# STM32.net
KiCad netlist of a schematic drawn in EAGLE
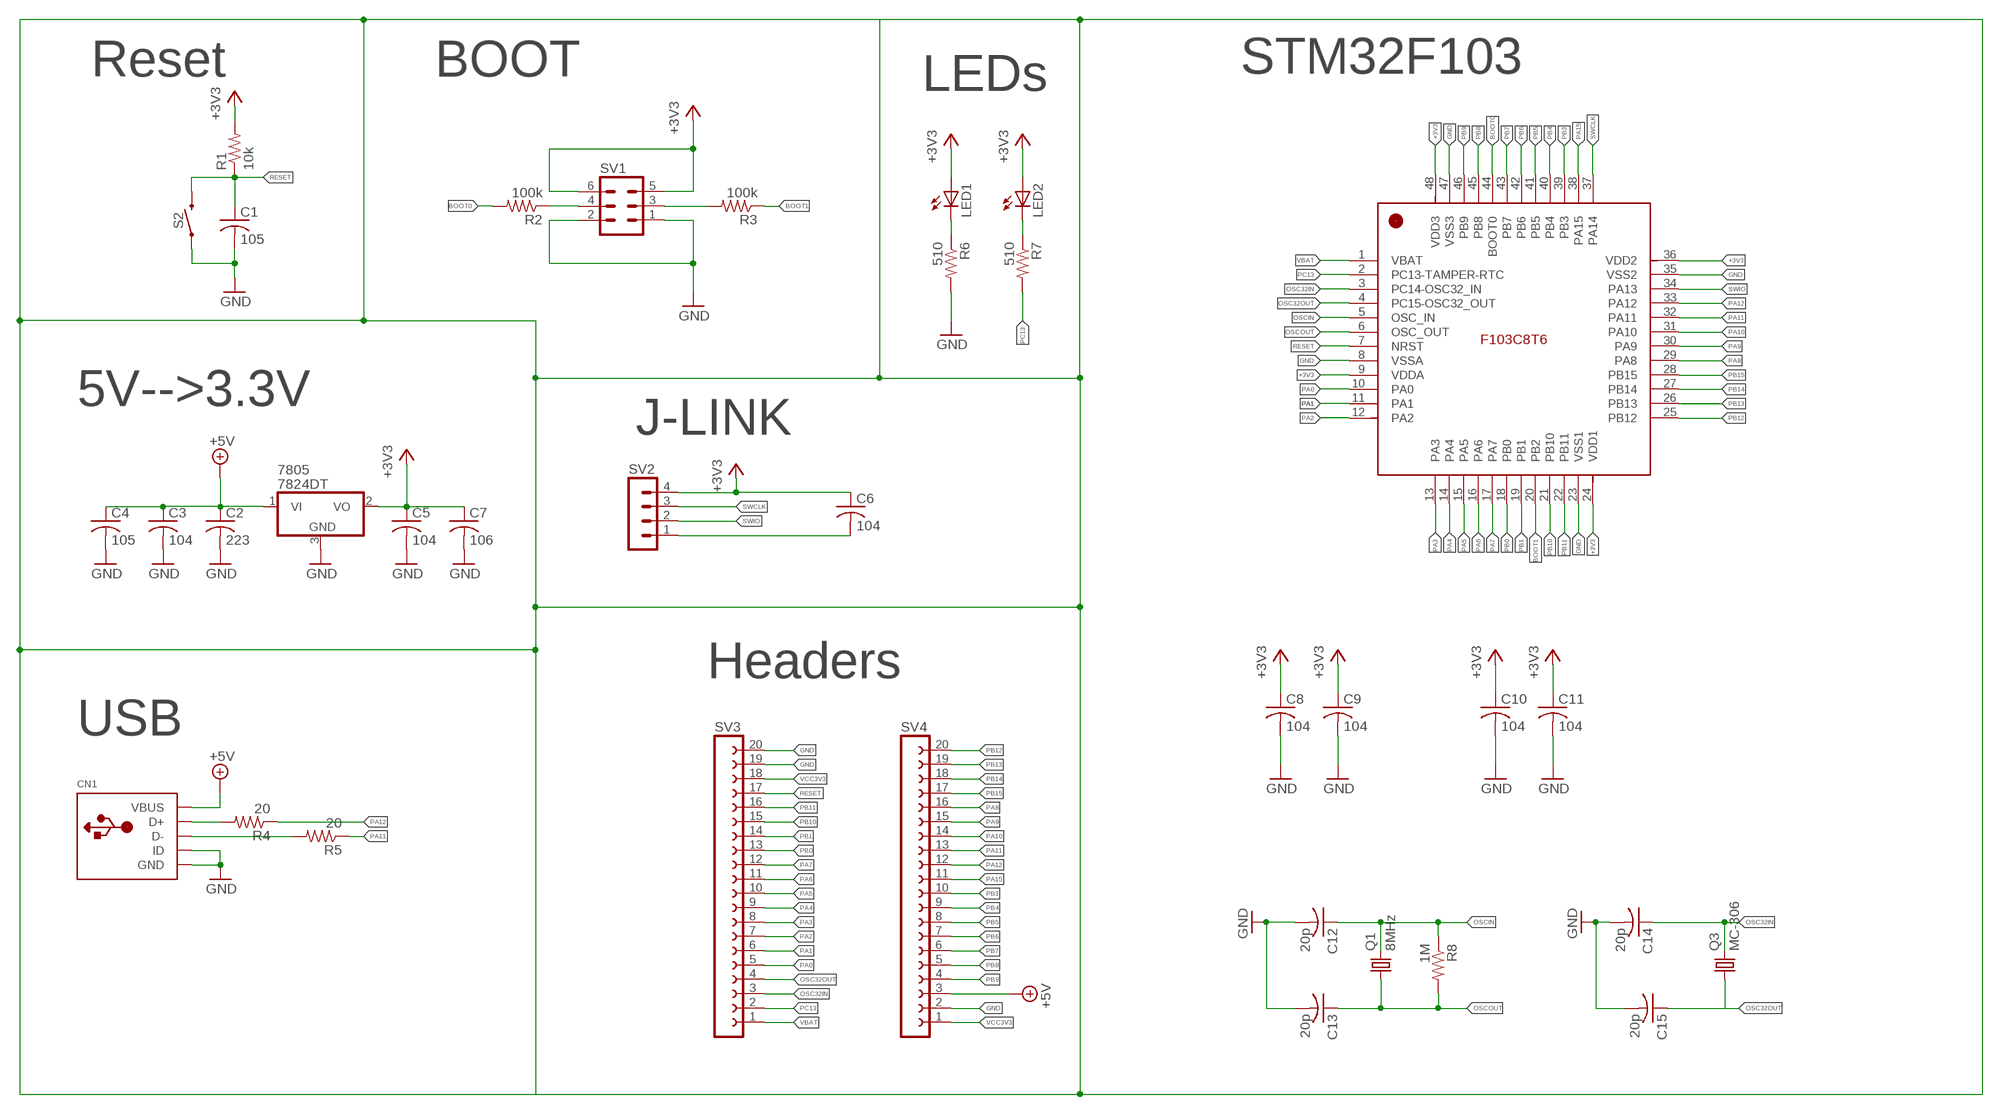
[diagram p0: schematic, sheet 1]

(export (version "E")
  (design (tool "Eeschema 10.0.6"))
  (components
    (comp (ref "7805")
      (value "7824DT")
      (footprint "eagle-import:TO252")
      (libsource (lib "eagle-import") (part "78DT24"))
    )
    (comp (ref "C1")
      (value "105")
      (footprint "eagle-import:C0603")
      (libsource (lib "eagle-import") (part "C-USC0603"))
    )
    (comp (ref "C2")
      (value "223")
      (footprint "eagle-import:C0603")
      (libsource (lib "eagle-import") (part "C-USC0603"))
    )
    (comp (ref "C3")
      (value "104")
      (footprint "eagle-import:C0603")
      (libsource (lib "eagle-import") (part "C-USC0603"))
    )
    (comp (ref "C4")
      (value "105")
      (footprint "eagle-import:C0805")
      (libsource (lib "eagle-import") (part "C-USC0805"))
    )
    (comp (ref "C5")
      (value "104")
      (footprint "eagle-import:C0603")
      (libsource (lib "eagle-import") (part "C-USC0603"))
    )
    (comp (ref "C6")
      (value "104")
      (footprint "eagle-import:C0603")
      (libsource (lib "eagle-import") (part "C-USC0603"))
    )
    (comp (ref "C7")
      (value "106")
      (footprint "eagle-import:C0805")
      (libsource (lib "eagle-import") (part "C-USC0805"))
    )
    (comp (ref "C8")
      (value "104")
      (footprint "eagle-import:C0603")
      (libsource (lib "eagle-import") (part "C-USC0603"))
    )
    (comp (ref "C9")
      (value "104")
      (footprint "eagle-import:C0603")
      (libsource (lib "eagle-import") (part "C-USC0603"))
    )
    (comp (ref "C10")
      (value "104")
      (footprint "eagle-import:C0603")
      (libsource (lib "eagle-import") (part "C-USC0603"))
    )
    (comp (ref "C11")
      (value "104")
      (footprint "eagle-import:C0603")
      (libsource (lib "eagle-import") (part "C-USC0603"))
    )
    (comp (ref "C12")
      (value "20p")
      (footprint "eagle-import:C0603")
      (libsource (lib "eagle-import") (part "C-USC0603"))
    )
    (comp (ref "C13")
      (value "20p")
      (footprint "eagle-import:C0603")
      (libsource (lib "eagle-import") (part "C-USC0603"))
    )
    (comp (ref "C14")
      (value "20p")
      (footprint "eagle-import:C0603")
      (libsource (lib "eagle-import") (part "C-USC0603"))
    )
    (comp (ref "C15")
      (value "20p")
      (footprint "eagle-import:C0603")
      (libsource (lib "eagle-import") (part "C-USC0603"))
    )
    (comp (ref "CN1")
      (value "USBMINIB")
      (footprint "eagle-import:USB-MINIB")
      (libsource (lib "eagle-import") (part "USBMINIB"))
    )
    (comp (ref "LED1")
      (value "LEDCHIPLED_0805")
      (footprint "eagle-import:CHIPLED_0805")
      (libsource (lib "eagle-import") (part "LEDCHIPLED_0805"))
    )
    (comp (ref "LED2")
      (value "LEDCHIPLED_0805")
      (footprint "eagle-import:CHIPLED_0805")
      (libsource (lib "eagle-import") (part "LEDCHIPLED_0805"))
    )
    (comp (ref "Q1")
      (value "8MHz")
      (footprint "eagle-import:HC49U70")
      (libsource (lib "eagle-import") (part "CRYTALHC49U70"))
    )
    (comp (ref "Q3")
      (value "MC-306")
      (footprint "eagle-import:MC-306")
      (fields (field (name "MPN") "MC-306 60.0KHZ  100PPM ,12.5PF"))
      (libsource (lib "eagle-import") (part "MC-306"))
    )
    (comp (ref "R1")
      (value "10k")
      (footprint "eagle-import:R0603")
      (libsource (lib "eagle-import") (part "R-US_R0603"))
    )
    (comp (ref "R2")
      (value "100k")
      (footprint "eagle-import:R0603")
      (libsource (lib "eagle-import") (part "R-US_R0603"))
    )
    (comp (ref "R3")
      (value "100k")
      (footprint "eagle-import:R0603")
      (libsource (lib "eagle-import") (part "R-US_R0603"))
    )
    (comp (ref "R4")
      (value "20")
      (footprint "eagle-import:R0603")
      (libsource (lib "eagle-import") (part "R-US_R0603"))
    )
    (comp (ref "R5")
      (value "20")
      (footprint "eagle-import:R0603")
      (libsource (lib "eagle-import") (part "R-US_R0603"))
    )
    (comp (ref "R6")
      (value "510")
      (footprint "eagle-import:R0603")
      (libsource (lib "eagle-import") (part "R-US_R0603"))
    )
    (comp (ref "R7")
      (value "510")
      (footprint "eagle-import:R0603")
      (libsource (lib "eagle-import") (part "R-US_R0603"))
    )
    (comp (ref "R8")
      (value "1M")
      (footprint "eagle-import:R0603")
      (libsource (lib "eagle-import") (part "R-US_R0603"))
    )
    (comp (ref "S2")
      (value "MOMENTARY-SWITCH-SPST-SMD-5.2-REDUNDANT")
      (footprint "eagle-import:TACTILE_SWITCH_SMD_5.2MM")
      (libsource (lib "eagle-import") (part "MOMENTARY-SWITCH-SPST-SMD-5.2-REDUNDANT"))
    )
    (comp (ref "SV1")
      (value "MA03-2")
      (footprint "eagle-import:MA03-2")
      (libsource (lib "eagle-import") (part "MA03-2"))
    )
    (comp (ref "SV2")
      (value "MA04-1")
      (footprint "eagle-import:MA04-1")
      (libsource (lib "eagle-import") (part "MA04-1"))
    )
    (comp (ref "SV3")
      (value "FE20-1")
      (footprint "eagle-import:FE20")
      (libsource (lib "eagle-import") (part "FE20-1"))
    )
    (comp (ref "SV4")
      (value "FE20-1")
      (footprint "eagle-import:FE20")
      (libsource (lib "eagle-import") (part "FE20-1"))
    )
    (comp (ref "U$1")
      (value "STM32F103C8T6")
      (footprint "eagle-import:LQFP48_7X7MM_0.5MMPP")
      (fields (field (name "MF") "STMicroelectronics"))
      (libsource (lib "eagle-import") (part "STM32F103C8T6"))
    )
  )
  (nets
    (net (code "1") (name "+3V3") (class "Default")
      (node (ref "7805") (pin "2") (pinfunction "VO_2") (pintype "passive"))
      (node (ref "C10") (pin "1") (pinfunction "1_1") (pintype "passive"))
      (node (ref "C11") (pin "1") (pinfunction "1_1") (pintype "passive"))
      (node (ref "C5") (pin "1") (pinfunction "1_1") (pintype "passive"))
      (node (ref "C6") (pin "1") (pinfunction "1_1") (pintype "passive"))
      (node (ref "C7") (pin "1") (pinfunction "1_1") (pintype "passive"))
      (node (ref "C8") (pin "1") (pinfunction "1_1") (pintype "passive"))
      (node (ref "C9") (pin "1") (pinfunction "1_1") (pintype "passive"))
      (node (ref "LED1") (pin "A") (pinfunction "A_A") (pintype "passive"))
      (node (ref "LED2") (pin "A") (pinfunction "A_A") (pintype "passive"))
      (node (ref "R1") (pin "2") (pinfunction "2_2") (pintype "passive"))
      (node (ref "SV1") (pin "5") (pinfunction "5_5") (pintype "passive"))
      (node (ref "SV1") (pin "6") (pinfunction "6_6") (pintype "passive"))
      (node (ref "SV2") (pin "4") (pinfunction "4_4") (pintype "passive"))
      (node (ref "U$1") (pin "24") (pinfunction "VDD1_24") (pintype "bidirectional"))
      (node (ref "U$1") (pin "36") (pinfunction "VDD2_36") (pintype "bidirectional"))
      (node (ref "U$1") (pin "48") (pinfunction "VDD3_48") (pintype "bidirectional"))
      (node (ref "U$1") (pin "9") (pinfunction "VDDA_9") (pintype "bidirectional"))
    )
    (net (code "2") (name "+5V") (class "Default")
      (node (ref "7805") (pin "1") (pinfunction "VI_1") (pintype "input"))
      (node (ref "C2") (pin "1") (pinfunction "1_1") (pintype "passive"))
      (node (ref "C3") (pin "1") (pinfunction "1_1") (pintype "passive"))
      (node (ref "C4") (pin "1") (pinfunction "1_1") (pintype "passive"))
      (node (ref "CN1") (pin "VBUS") (pinfunction "VBUS_VBUS") (pintype "power_in"))
      (node (ref "SV4") (pin "3") (pinfunction "3_3") (pintype "passive"))
    )
    (net (code "3") (name "BOOT0") (class "Default")
      (node (ref "R2") (pin "2") (pinfunction "2_2") (pintype "passive"))
      (node (ref "U$1") (pin "44") (pinfunction "BOOT0_44") (pintype "bidirectional"))
    )
    (net (code "4") (name "BOOT1") (class "Default")
      (node (ref "R3") (pin "1") (pinfunction "1_1") (pintype "passive"))
      (node (ref "U$1") (pin "20") (pinfunction "PB2_20") (pintype "bidirectional"))
    )
    (net (code "5") (name "GND") (class "Default")
      (node (ref "7805") (pin "3") (pinfunction "GND_3") (pintype "passive"))
      (node (ref "C1") (pin "2") (pinfunction "2_2") (pintype "passive"))
      (node (ref "C10") (pin "2") (pinfunction "2_2") (pintype "passive"))
      (node (ref "C11") (pin "2") (pinfunction "2_2") (pintype "passive"))
      (node (ref "C12") (pin "2") (pinfunction "2_2") (pintype "passive"))
      (node (ref "C13") (pin "2") (pinfunction "2_2") (pintype "passive"))
      (node (ref "C14") (pin "2") (pinfunction "2_2") (pintype "passive"))
      (node (ref "C15") (pin "2") (pinfunction "2_2") (pintype "passive"))
      (node (ref "C2") (pin "2") (pinfunction "2_2") (pintype "passive"))
      (node (ref "C3") (pin "2") (pinfunction "2_2") (pintype "passive"))
      (node (ref "C4") (pin "2") (pinfunction "2_2") (pintype "passive"))
      (node (ref "C5") (pin "2") (pinfunction "2_2") (pintype "passive"))
      (node (ref "C7") (pin "2") (pinfunction "2_2") (pintype "passive"))
      (node (ref "C8") (pin "2") (pinfunction "2_2") (pintype "passive"))
      (node (ref "C9") (pin "2") (pinfunction "2_2") (pintype "passive"))
      (node (ref "CN1") (pin "GND") (pinfunction "GND_GND") (pintype "power_in"))
      (node (ref "CN1") (pin "ID") (pinfunction "ID_ID") (pintype "bidirectional"))
      (node (ref "R6") (pin "2") (pinfunction "2_2") (pintype "passive"))
      (node (ref "S2") (pin "1") (pinfunction "1_1") (pintype "passive"))
      (node (ref "S2") (pin "2") (pinfunction "1_2") (pintype "passive"))
      (node (ref "SV1") (pin "1") (pinfunction "1_1") (pintype "passive"))
      (node (ref "SV1") (pin "2") (pinfunction "2_2") (pintype "passive"))
      (node (ref "SV3") (pin "19") (pinfunction "19_19") (pintype "passive"))
      (node (ref "SV3") (pin "20") (pinfunction "20_20") (pintype "passive"))
      (node (ref "SV4") (pin "2") (pinfunction "2_2") (pintype "passive"))
      (node (ref "U$1") (pin "23") (pinfunction "VSS1_23") (pintype "bidirectional"))
      (node (ref "U$1") (pin "35") (pinfunction "VSS2_35") (pintype "bidirectional"))
      (node (ref "U$1") (pin "47") (pinfunction "VSS3_47") (pintype "bidirectional"))
      (node (ref "U$1") (pin "8") (pinfunction "VSSA_8") (pintype "bidirectional"))
    )
    (net (code "6") (name "Net-(C6-Pad2)") (class "Default")
      (node (ref "C6") (pin "2") (pinfunction "2_2") (pintype "passive"))
      (node (ref "SV2") (pin "1") (pinfunction "1_1") (pintype "passive"))
    )
    (net (code "7") (name "Net-(CN1-PadD+)") (class "Default")
      (node (ref "CN1") (pin "D+") (pinfunction "D+_D+") (pintype "bidirectional"))
      (node (ref "R4") (pin "2") (pinfunction "2_2") (pintype "passive"))
    )
    (net (code "8") (name "Net-(CN1-PadD-)") (class "Default")
      (node (ref "CN1") (pin "D-") (pinfunction "D-_D-") (pintype "bidirectional"))
      (node (ref "R5") (pin "2") (pinfunction "2_2") (pintype "passive"))
    )
    (net (code "9") (name "Net-(LED1-PadC)") (class "Default")
      (node (ref "LED1") (pin "C") (pinfunction "C_C") (pintype "passive"))
      (node (ref "R6") (pin "1") (pinfunction "1_1") (pintype "passive"))
    )
    (net (code "10") (name "Net-(LED2-PadC)") (class "Default")
      (node (ref "LED2") (pin "C") (pinfunction "C_C") (pintype "passive"))
      (node (ref "R7") (pin "1") (pinfunction "1_1") (pintype "passive"))
    )
    (net (code "11") (name "Net-(R2-Pad1)") (class "Default")
      (node (ref "R2") (pin "1") (pinfunction "1_1") (pintype "passive"))
      (node (ref "SV1") (pin "4") (pinfunction "4_4") (pintype "passive"))
    )
    (net (code "12") (name "Net-(R3-Pad2)") (class "Default")
      (node (ref "R3") (pin "2") (pinfunction "2_2") (pintype "passive"))
      (node (ref "SV1") (pin "3") (pinfunction "3_3") (pintype "passive"))
    )
    (net (code "13") (name "OSC32IN") (class "Default")
      (node (ref "C14") (pin "1") (pinfunction "1_1") (pintype "passive"))
      (node (ref "Q3") (pin "4") (pinfunction "2_4") (pintype "passive"))
      (node (ref "SV3") (pin "3") (pinfunction "3_3") (pintype "passive"))
      (node (ref "U$1") (pin "3") (pinfunction "PC14-OSC32_IN_3") (pintype "bidirectional"))
    )
    (net (code "14") (name "OSC32OUT") (class "Default")
      (node (ref "C15") (pin "1") (pinfunction "1_1") (pintype "passive"))
      (node (ref "Q3") (pin "1") (pinfunction "1_1") (pintype "passive"))
      (node (ref "SV3") (pin "4") (pinfunction "4_4") (pintype "passive"))
      (node (ref "U$1") (pin "4") (pinfunction "PC15-OSC32_OUT_4") (pintype "bidirectional"))
    )
    (net (code "15") (name "OSCIN") (class "Default")
      (node (ref "C12") (pin "1") (pinfunction "1_1") (pintype "passive"))
      (node (ref "Q1") (pin "2") (pinfunction "2_2") (pintype "passive"))
      (node (ref "R8") (pin "1") (pinfunction "1_1") (pintype "passive"))
      (node (ref "U$1") (pin "5") (pinfunction "OSC_IN_5") (pintype "bidirectional"))
    )
    (net (code "16") (name "OSCOUT") (class "Default")
      (node (ref "C13") (pin "1") (pinfunction "1_1") (pintype "passive"))
      (node (ref "Q1") (pin "1") (pinfunction "1_1") (pintype "passive"))
      (node (ref "R8") (pin "2") (pinfunction "2_2") (pintype "passive"))
      (node (ref "U$1") (pin "6") (pinfunction "OSC_OUT_6") (pintype "bidirectional"))
    )
    (net (code "17") (name "PA0") (class "Default")
      (node (ref "SV3") (pin "5") (pinfunction "5_5") (pintype "passive"))
      (node (ref "U$1") (pin "10") (pinfunction "PA0_10") (pintype "bidirectional"))
    )
    (net (code "18") (name "PA1") (class "Default")
      (node (ref "SV3") (pin "6") (pinfunction "6_6") (pintype "passive"))
      (node (ref "U$1") (pin "11") (pinfunction "PA1_11") (pintype "bidirectional"))
    )
    (net (code "19") (name "PA2") (class "Default")
      (node (ref "SV3") (pin "7") (pinfunction "7_7") (pintype "passive"))
      (node (ref "U$1") (pin "12") (pinfunction "PA2_12") (pintype "bidirectional"))
    )
    (net (code "20") (name "PA3") (class "Default")
      (node (ref "SV3") (pin "8") (pinfunction "8_8") (pintype "passive"))
      (node (ref "U$1") (pin "13") (pinfunction "PA3_13") (pintype "bidirectional"))
    )
    (net (code "21") (name "PA4") (class "Default")
      (node (ref "SV3") (pin "9") (pinfunction "9_9") (pintype "passive"))
      (node (ref "U$1") (pin "14") (pinfunction "PA4_14") (pintype "bidirectional"))
    )
    (net (code "22") (name "PA5") (class "Default")
      (node (ref "SV3") (pin "10") (pinfunction "10_10") (pintype "passive"))
      (node (ref "U$1") (pin "15") (pinfunction "PA5_15") (pintype "bidirectional"))
    )
    (net (code "23") (name "PA6") (class "Default")
      (node (ref "SV3") (pin "11") (pinfunction "11_11") (pintype "passive"))
      (node (ref "U$1") (pin "16") (pinfunction "PA6_16") (pintype "bidirectional"))
    )
    (net (code "24") (name "PA7") (class "Default")
      (node (ref "SV3") (pin "12") (pinfunction "12_12") (pintype "passive"))
      (node (ref "U$1") (pin "17") (pinfunction "PA7_17") (pintype "bidirectional"))
    )
    (net (code "25") (name "PA8") (class "Default")
      (node (ref "SV4") (pin "16") (pinfunction "16_16") (pintype "passive"))
      (node (ref "U$1") (pin "29") (pinfunction "PA8_29") (pintype "bidirectional"))
    )
    (net (code "26") (name "PA9") (class "Default")
      (node (ref "SV4") (pin "15") (pinfunction "15_15") (pintype "passive"))
      (node (ref "U$1") (pin "30") (pinfunction "PA9_30") (pintype "bidirectional"))
    )
    (net (code "27") (name "PA10") (class "Default")
      (node (ref "SV4") (pin "14") (pinfunction "14_14") (pintype "passive"))
      (node (ref "U$1") (pin "31") (pinfunction "PA10_31") (pintype "bidirectional"))
    )
    (net (code "28") (name "PA11") (class "Default")
      (node (ref "R5") (pin "1") (pinfunction "1_1") (pintype "passive"))
      (node (ref "SV4") (pin "13") (pinfunction "13_13") (pintype "passive"))
      (node (ref "U$1") (pin "32") (pinfunction "PA11_32") (pintype "bidirectional"))
    )
    (net (code "29") (name "PA12") (class "Default")
      (node (ref "R4") (pin "1") (pinfunction "1_1") (pintype "passive"))
      (node (ref "SV4") (pin "12") (pinfunction "12_12") (pintype "passive"))
      (node (ref "U$1") (pin "33") (pinfunction "PA12_33") (pintype "bidirectional"))
    )
    (net (code "30") (name "PA15") (class "Default")
      (node (ref "SV4") (pin "11") (pinfunction "11_11") (pintype "passive"))
      (node (ref "U$1") (pin "38") (pinfunction "PA15_38") (pintype "bidirectional"))
    )
    (net (code "31") (name "PB0") (class "Default")
      (node (ref "SV3") (pin "13") (pinfunction "13_13") (pintype "passive"))
      (node (ref "U$1") (pin "18") (pinfunction "PB0_18") (pintype "bidirectional"))
    )
    (net (code "32") (name "PB1") (class "Default")
      (node (ref "SV3") (pin "14") (pinfunction "14_14") (pintype "passive"))
      (node (ref "U$1") (pin "19") (pinfunction "PB1_19") (pintype "bidirectional"))
    )
    (net (code "33") (name "PB3") (class "Default")
      (node (ref "SV4") (pin "10") (pinfunction "10_10") (pintype "passive"))
      (node (ref "U$1") (pin "39") (pinfunction "PB3_39") (pintype "bidirectional"))
    )
    (net (code "34") (name "PB4") (class "Default")
      (node (ref "SV4") (pin "9") (pinfunction "9_9") (pintype "passive"))
      (node (ref "U$1") (pin "40") (pinfunction "PB4_40") (pintype "bidirectional"))
    )
    (net (code "35") (name "PB5") (class "Default")
      (node (ref "SV4") (pin "8") (pinfunction "8_8") (pintype "passive"))
      (node (ref "U$1") (pin "41") (pinfunction "PB5_41") (pintype "bidirectional"))
    )
    (net (code "36") (name "PB6") (class "Default")
      (node (ref "SV4") (pin "7") (pinfunction "7_7") (pintype "passive"))
      (node (ref "U$1") (pin "42") (pinfunction "PB6_42") (pintype "bidirectional"))
    )
    (net (code "37") (name "PB7") (class "Default")
      (node (ref "SV4") (pin "6") (pinfunction "6_6") (pintype "passive"))
      (node (ref "U$1") (pin "43") (pinfunction "PB7_43") (pintype "bidirectional"))
    )
    (net (code "38") (name "PB8") (class "Default")
      (node (ref "SV4") (pin "5") (pinfunction "5_5") (pintype "passive"))
      (node (ref "U$1") (pin "45") (pinfunction "PB8_45") (pintype "bidirectional"))
    )
    (net (code "39") (name "PB9") (class "Default")
      (node (ref "SV4") (pin "4") (pinfunction "4_4") (pintype "passive"))
      (node (ref "U$1") (pin "46") (pinfunction "PB9_46") (pintype "bidirectional"))
    )
    (net (code "40") (name "PB10") (class "Default")
      (node (ref "SV3") (pin "15") (pinfunction "15_15") (pintype "passive"))
      (node (ref "U$1") (pin "21") (pinfunction "PB10_21") (pintype "bidirectional"))
    )
    (net (code "41") (name "PB11") (class "Default")
      (node (ref "SV3") (pin "16") (pinfunction "16_16") (pintype "passive"))
      (node (ref "U$1") (pin "22") (pinfunction "PB11_22") (pintype "bidirectional"))
    )
    (net (code "42") (name "PB12") (class "Default")
      (node (ref "SV4") (pin "20") (pinfunction "20_20") (pintype "passive"))
      (node (ref "U$1") (pin "25") (pinfunction "PB12_25") (pintype "bidirectional"))
    )
    (net (code "43") (name "PB13") (class "Default")
      (node (ref "SV4") (pin "19") (pinfunction "19_19") (pintype "passive"))
      (node (ref "U$1") (pin "26") (pinfunction "PB13_26") (pintype "bidirectional"))
    )
    (net (code "44") (name "PB14") (class "Default")
      (node (ref "SV4") (pin "18") (pinfunction "18_18") (pintype "passive"))
      (node (ref "U$1") (pin "27") (pinfunction "PB14_27") (pintype "bidirectional"))
    )
    (net (code "45") (name "PB15") (class "Default")
      (node (ref "SV4") (pin "17") (pinfunction "17_17") (pintype "passive"))
      (node (ref "U$1") (pin "28") (pinfunction "PB15_28") (pintype "bidirectional"))
    )
    (net (code "46") (name "PC13") (class "Default")
      (node (ref "R7") (pin "2") (pinfunction "2_2") (pintype "passive"))
      (node (ref "SV3") (pin "2") (pinfunction "2_2") (pintype "passive"))
      (node (ref "U$1") (pin "2") (pinfunction "PC13-TAMPER-RTC_2") (pintype "bidirectional"))
    )
    (net (code "47") (name "RESET") (class "Default")
      (node (ref "C1") (pin "1") (pinfunction "1_1") (pintype "passive"))
      (node (ref "R1") (pin "1") (pinfunction "1_1") (pintype "passive"))
      (node (ref "S2") (pin "3") (pinfunction "2_3") (pintype "passive"))
      (node (ref "S2") (pin "4") (pinfunction "2_4") (pintype "passive"))
      (node (ref "SV3") (pin "17") (pinfunction "17_17") (pintype "passive"))
      (node (ref "U$1") (pin "7") (pinfunction "NRST_7") (pintype "bidirectional"))
    )
    (net (code "48") (name "SWCLK") (class "Default")
      (node (ref "SV2") (pin "3") (pinfunction "3_3") (pintype "passive"))
      (node (ref "U$1") (pin "37") (pinfunction "PA14_37") (pintype "bidirectional"))
    )
    (net (code "49") (name "SWIO") (class "Default")
      (node (ref "SV2") (pin "2") (pinfunction "2_2") (pintype "passive"))
      (node (ref "U$1") (pin "34") (pinfunction "PA13_34") (pintype "bidirectional"))
    )
    (net (code "50") (name "VBAT") (class "Default")
      (node (ref "SV3") (pin "1") (pinfunction "1_1") (pintype "passive"))
      (node (ref "U$1") (pin "1") (pinfunction "VBAT_1") (pintype "bidirectional"))
    )
    (net (code "51") (name "VCC3V3") (class "Default")
      (node (ref "SV3") (pin "18") (pinfunction "18_18") (pintype "passive"))
      (node (ref "SV4") (pin "1") (pinfunction "1_1") (pintype "passive"))
    )
  )
)
